# PCB0814.net
KiCad netlist of a schematic drawn in Altium Designer
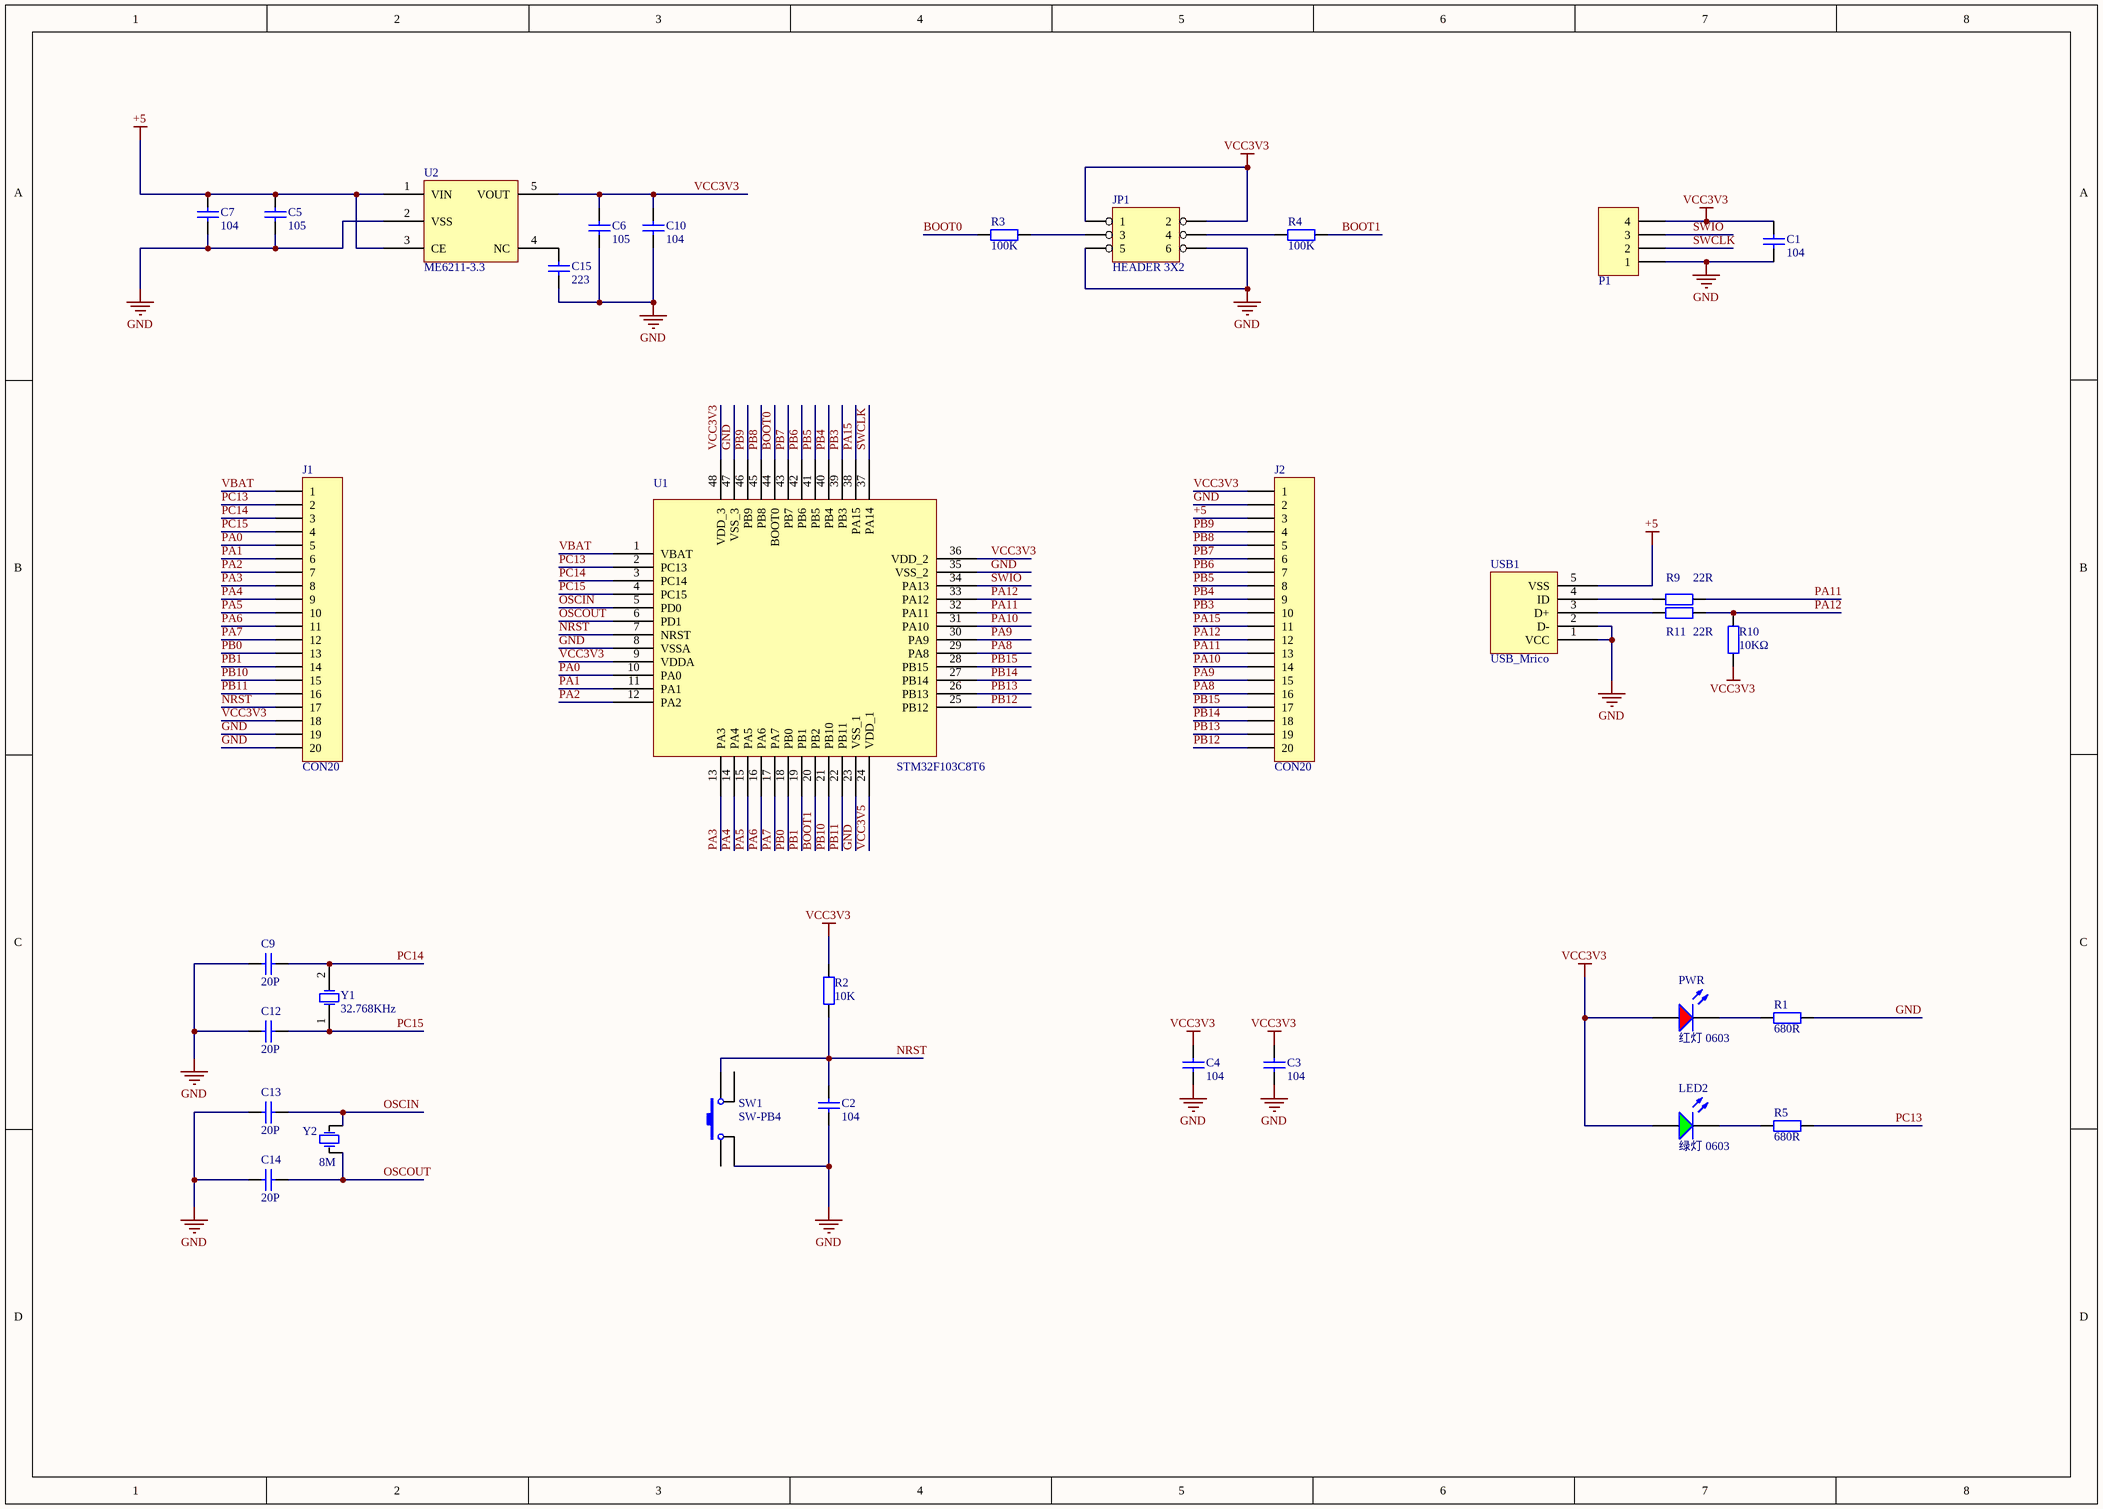
[diagram p0: PCB0814.SchDoc]

(export (version "E")
  (design (tool "Eeschema 10.0.6"))
  (components
    (comp (ref "C1")
      (value "104")
      (footprint "0603_C")
      (description "贴片电容")
      (libsource (lib "Cap") (part "0603 1uF (105) 10% 50V"))
    )
    (comp (ref "C2")
      (value "104")
      (footprint "0603_C")
      (description "贴片电容")
      (libsource (lib "Cap") (part "0603 1uF (105) 10% 50V"))
    )
    (comp (ref "C3")
      (value "104")
      (footprint "0603_C")
      (description "贴片电容")
      (libsource (lib "Cap") (part "0603 68pF (680) 5% 50V"))
    )
    (comp (ref "C4")
      (value "104")
      (footprint "0603_C")
      (description "贴片电容")
      (libsource (lib "Cap") (part "0603 68pF (680) 5% 50V"))
    )
    (comp (ref "C5")
      (value "105")
      (footprint "0603_C")
      (description "贴片电容")
      (libsource (lib "Cap") (part "0603 1uF (105) 10% 50V"))
    )
    (comp (ref "C6")
      (value "105")
      (footprint "0603_C")
      (description "贴片电容")
      (libsource (lib "Cap") (part "0603 1uF (105) 10% 50V"))
    )
    (comp (ref "C7")
      (value "104")
      (footprint "0603_C")
      (description "贴片电容")
      (libsource (lib "Cap") (part "0603 1uF (105) 10% 50V"))
    )
    (comp (ref "C9")
      (value "20P")
      (footprint "0603_C")
      (description "贴片电容")
      (libsource (lib "Cap") (part "0603 68pF (680) 5% 50V"))
    )
    (comp (ref "C10")
      (value "104")
      (footprint "0603_C")
      (description "贴片电容")
      (libsource (lib "Cap") (part "0603 1uF (105) 10% 50V"))
    )
    (comp (ref "C12")
      (value "20P")
      (footprint "0603_C")
      (description "贴片电容")
      (libsource (lib "Cap") (part "0603 68pF (680) 5% 50V"))
    )
    (comp (ref "C13")
      (value "20P")
      (footprint "0603_C")
      (description "贴片电容")
      (libsource (lib "Cap") (part "0603 68pF (680) 5% 50V"))
    )
    (comp (ref "C14")
      (value "20P")
      (footprint "0603_C")
      (description "贴片电容")
      (libsource (lib "Cap") (part "0603 68pF (680) 5% 50V"))
    )
    (comp (ref "C15")
      (value "223")
      (footprint "0603_C")
      (description "贴片电容")
      (libsource (lib "Cap") (part "0603 1uF (105) 10% 50V"))
    )
    (comp (ref "J1")
      (value "CON20")
      (footprint "HDR1X20")
      (description "Connector")
      (libsource (lib "Miscellaneous Devices") (part "CON20"))
    )
    (comp (ref "J2")
      (value "CON20")
      (footprint "HDR1X20")
      (description "Connector")
      (libsource (lib "Miscellaneous Devices") (part "CON20"))
    )
    (comp (ref "JP1")
      (value "HEADER 3X2")
      (footprint "HDR2X3")
      (libsource (lib "Miscellaneous Devices") (part "HEADER 3X2"))
    )
    (comp (ref "LED2")
      (value "绿灯 0603")
      (footprint "0603_LED_S1")
      (description "发光二极管")
      (libsource (lib "LED") (part "0603 绿灯"))
    )
    (comp (ref "P1")
      (value "Header 4")
      (footprint "HDR4X1_A")
      (description "接插件")
      (fields (field (name "PUBLISHER") "Altium Limited"))
      (libsource (lib "Fszhang") (part "Header 4"))
    )
    (comp (ref "PWR")
      (value "红灯 0603")
      (footprint "0603_LED_S1")
      (description "发光二极管")
      (libsource (lib "LED") (part "0603 红灯"))
    )
    (comp (ref "R1")
      (value "680R")
      (footprint "0603_R")
      (description "贴片电阻")
      (libsource (lib "RES") (part "0603 1KΩ (1001) 1%"))
    )
    (comp (ref "R2")
      (value "10K")
      (footprint "0603_R")
      (description "贴片电阻")
      (libsource (lib "") (part "0603 1KΩ (1001) 1%_1"))
    )
    (comp (ref "R3")
      (value "100K")
      (footprint "0603_R")
      (description "贴片电阻")
      (libsource (lib "RES") (part "0603 1KΩ (1001) 1%"))
    )
    (comp (ref "R4")
      (value "100K")
      (footprint "0603_R")
      (description "贴片电阻")
      (libsource (lib "RES") (part "0603 1KΩ (1001) 1%"))
    )
    (comp (ref "R5")
      (value "680R")
      (footprint "0603_R")
      (description "贴片电阻")
      (libsource (lib "RES") (part "0603 1KΩ (1001) 1%"))
    )
    (comp (ref "R9")
      (value "22R")
      (footprint "0603_R")
      (description "贴片电阻")
      (libsource (lib "RES") (part "0603 22Ω (22R0) 1%"))
    )
    (comp (ref "R10")
      (value "10KΩ")
      (footprint "0603_R")
      (description "贴片电阻")
      (libsource (lib "RES") (part "0603 2KΩ (2001) 1%"))
    )
    (comp (ref "R11")
      (value "22R")
      (footprint "0603_R")
      (description "贴片电阻")
      (libsource (lib "RES") (part "0603 22Ω (22R0) 1%"))
    )
    (comp (ref "SW1")
      (value "SW-PB4")
      (footprint "SW_PB4_A1")
      (description "微动开关")
      (fields (field (name "PUBLISHER") "Altium Limited"))
      (libsource (lib "Fszhang") (part "SW-PB4"))
    )
    (comp (ref "U1")
      (value "STM32F103C8T6")
      (footprint "LQFP-48")
      (libsource (lib "PCB0814") (part "STM32F103C8T6"))
    )
    (comp (ref "U2")
      (value "ME6211-3.3")
      (footprint "SOT-23-5")
      (libsource (lib "PCB0814") (part "ME6211-3.3"))
    )
    (comp (ref "USB1")
      (value "USB_Mrico")
      (footprint "USB_MICRO")
      (description "MicroUSB接口")
      (libsource (lib "Fszhang") (part "USB_M"))
    )
    (comp (ref "Y1")
      (value "32.768KHz")
      (footprint "SMD-5032_2P")
      (description "贴片晶振")
      (libsource (lib "Miscellaneous Devices LC") (part "SMD-5032_2P 11.0592MHZ 20PF 20PPM"))
    )
    (comp (ref "Y2")
      (value "8M")
      (footprint "X-SM49")
      (description "晶振")
      (fields (field (name "Comment") "XTAL") (field (name "PUBLISHER") "Altium Limited"))
      (libsource (lib "Fszhang") (part "XTAL"))
    )
  )
  (nets
    (net (code "1") (name "+5") (class "Default")
      (node (ref "C5") (pin "2") (pinfunction "2_2") (pintype "passive"))
      (node (ref "C7") (pin "2") (pinfunction "2_2") (pintype "passive"))
      (node (ref "J2") (pin "3") (pinfunction "3_3") (pintype "passive"))
      (node (ref "U2") (pin "1") (pinfunction "VIN_1") (pintype "passive"))
      (node (ref "U2") (pin "3") (pinfunction "CE_3") (pintype "passive"))
      (node (ref "USB1") (pin "5") (pinfunction "VSS_5") (pintype "passive"))
    )
    (net (code "2") (name "/BOOT0") (class "Default")
      (node (ref "R3") (pin "1") (pinfunction "1_1") (pintype "passive"))
      (node (ref "U1") (pin "44") (pinfunction "BOOT0_44") (pintype "passive"))
    )
    (net (code "3") (name "/BOOT1") (class "Default")
      (node (ref "R4") (pin "2") (pinfunction "2_2") (pintype "passive"))
      (node (ref "U1") (pin "20") (pinfunction "PB2_20") (pintype "passive"))
    )
    (net (code "4") (name "/NRST") (class "Default")
      (node (ref "C2") (pin "2") (pinfunction "2_2") (pintype "passive"))
      (node (ref "J1") (pin "17") (pinfunction "17_17") (pintype "passive"))
      (node (ref "R2") (pin "1") (pinfunction "1_1") (pintype "passive"))
      (node (ref "SW1") (pin "2") (pinfunction "2_2") (pintype "passive"))
      (node (ref "U1") (pin "7") (pinfunction "NRST_7") (pintype "passive"))
    )
    (net (code "5") (name "/OSCIN") (class "Default")
      (node (ref "C13") (pin "2") (pinfunction "2_2") (pintype "passive"))
      (node (ref "U1") (pin "5") (pinfunction "PD0_5") (pintype "passive"))
      (node (ref "Y2") (pin "2") (pinfunction "OSC2_2") (pintype "passive"))
    )
    (net (code "6") (name "/OSCOUT") (class "Default")
      (node (ref "C14") (pin "2") (pinfunction "2_2") (pintype "passive"))
      (node (ref "U1") (pin "6") (pinfunction "PD1_6") (pintype "passive"))
      (node (ref "Y2") (pin "1") (pinfunction "OSC1_1") (pintype "passive"))
    )
    (net (code "7") (name "/PA0") (class "Default")
      (node (ref "J1") (pin "5") (pinfunction "5_5") (pintype "passive"))
      (node (ref "U1") (pin "10") (pinfunction "PA0_10") (pintype "passive"))
    )
    (net (code "8") (name "/PA1") (class "Default")
      (node (ref "J1") (pin "6") (pinfunction "6_6") (pintype "passive"))
      (node (ref "U1") (pin "11") (pinfunction "PA1_11") (pintype "passive"))
    )
    (net (code "9") (name "/PA2") (class "Default")
      (node (ref "J1") (pin "7") (pinfunction "7_7") (pintype "passive"))
      (node (ref "U1") (pin "12") (pinfunction "PA2_12") (pintype "passive"))
    )
    (net (code "10") (name "/PA3") (class "Default")
      (node (ref "J1") (pin "8") (pinfunction "8_8") (pintype "passive"))
      (node (ref "U1") (pin "13") (pinfunction "PA3_13") (pintype "passive"))
    )
    (net (code "11") (name "/PA4") (class "Default")
      (node (ref "J1") (pin "9") (pinfunction "9_9") (pintype "passive"))
      (node (ref "U1") (pin "14") (pinfunction "PA4_14") (pintype "passive"))
    )
    (net (code "12") (name "/PA5") (class "Default")
      (node (ref "J1") (pin "10") (pinfunction "10_10") (pintype "passive"))
      (node (ref "U1") (pin "15") (pinfunction "PA5_15") (pintype "passive"))
    )
    (net (code "13") (name "/PA6") (class "Default")
      (node (ref "J1") (pin "11") (pinfunction "11_11") (pintype "passive"))
      (node (ref "U1") (pin "16") (pinfunction "PA6_16") (pintype "passive"))
    )
    (net (code "14") (name "/PA7") (class "Default")
      (node (ref "J1") (pin "12") (pinfunction "12_12") (pintype "passive"))
      (node (ref "U1") (pin "17") (pinfunction "PA7_17") (pintype "passive"))
    )
    (net (code "15") (name "/PA8") (class "Default")
      (node (ref "J2") (pin "16") (pinfunction "16_16") (pintype "passive"))
      (node (ref "U1") (pin "29") (pinfunction "PA8_29") (pintype "passive"))
    )
    (net (code "16") (name "/PA9") (class "Default")
      (node (ref "J2") (pin "15") (pinfunction "15_15") (pintype "passive"))
      (node (ref "U1") (pin "30") (pinfunction "PA9_30") (pintype "passive"))
    )
    (net (code "17") (name "/PA10") (class "Default")
      (node (ref "J2") (pin "14") (pinfunction "14_14") (pintype "passive"))
      (node (ref "U1") (pin "31") (pinfunction "PA10_31") (pintype "passive"))
    )
    (net (code "18") (name "/PA11") (class "Default")
      (node (ref "J2") (pin "13") (pinfunction "13_13") (pintype "passive"))
      (node (ref "R9") (pin "2") (pinfunction "2_2") (pintype "passive"))
      (node (ref "U1") (pin "32") (pinfunction "PA11_32") (pintype "passive"))
    )
    (net (code "19") (name "/PA12") (class "Default")
      (node (ref "J2") (pin "12") (pinfunction "12_12") (pintype "passive"))
      (node (ref "R10") (pin "2") (pinfunction "2_2") (pintype "passive"))
      (node (ref "R11") (pin "2") (pinfunction "2_2") (pintype "passive"))
      (node (ref "U1") (pin "33") (pinfunction "PA12_33") (pintype "passive"))
    )
    (net (code "20") (name "/PA15") (class "Default")
      (node (ref "J2") (pin "11") (pinfunction "11_11") (pintype "passive"))
      (node (ref "U1") (pin "38") (pinfunction "PA15_38") (pintype "passive"))
    )
    (net (code "21") (name "/PB0") (class "Default")
      (node (ref "J1") (pin "13") (pinfunction "13_13") (pintype "passive"))
      (node (ref "U1") (pin "18") (pinfunction "PB0_18") (pintype "passive"))
    )
    (net (code "22") (name "/PB1") (class "Default")
      (node (ref "J1") (pin "14") (pinfunction "14_14") (pintype "passive"))
      (node (ref "U1") (pin "19") (pinfunction "PB1_19") (pintype "passive"))
    )
    (net (code "23") (name "/PB3") (class "Default")
      (node (ref "J2") (pin "10") (pinfunction "10_10") (pintype "passive"))
      (node (ref "U1") (pin "39") (pinfunction "PB3_39") (pintype "passive"))
    )
    (net (code "24") (name "/PB4") (class "Default")
      (node (ref "J2") (pin "9") (pinfunction "9_9") (pintype "passive"))
      (node (ref "U1") (pin "40") (pinfunction "PB4_40") (pintype "passive"))
    )
    (net (code "25") (name "/PB5") (class "Default")
      (node (ref "J2") (pin "8") (pinfunction "8_8") (pintype "passive"))
      (node (ref "U1") (pin "41") (pinfunction "PB5_41") (pintype "passive"))
    )
    (net (code "26") (name "/PB6") (class "Default")
      (node (ref "J2") (pin "7") (pinfunction "7_7") (pintype "passive"))
      (node (ref "U1") (pin "42") (pinfunction "PB6_42") (pintype "passive"))
    )
    (net (code "27") (name "/PB7") (class "Default")
      (node (ref "J2") (pin "6") (pinfunction "6_6") (pintype "passive"))
      (node (ref "U1") (pin "43") (pinfunction "PB7_43") (pintype "passive"))
    )
    (net (code "28") (name "/PB8") (class "Default")
      (node (ref "J2") (pin "5") (pinfunction "5_5") (pintype "passive"))
      (node (ref "U1") (pin "45") (pinfunction "PB8_45") (pintype "passive"))
    )
    (net (code "29") (name "/PB9") (class "Default")
      (node (ref "J2") (pin "4") (pinfunction "4_4") (pintype "passive"))
      (node (ref "U1") (pin "46") (pinfunction "PB9_46") (pintype "passive"))
    )
    (net (code "30") (name "/PB10") (class "Default")
      (node (ref "J1") (pin "15") (pinfunction "15_15") (pintype "passive"))
      (node (ref "U1") (pin "21") (pinfunction "PB10_21") (pintype "passive"))
    )
    (net (code "31") (name "/PB11") (class "Default")
      (node (ref "J1") (pin "16") (pinfunction "16_16") (pintype "passive"))
      (node (ref "U1") (pin "22") (pinfunction "PB11_22") (pintype "passive"))
    )
    (net (code "32") (name "/PB12") (class "Default")
      (node (ref "J2") (pin "20") (pinfunction "20_20") (pintype "passive"))
      (node (ref "U1") (pin "25") (pinfunction "PB12_25") (pintype "passive"))
    )
    (net (code "33") (name "/PB13") (class "Default")
      (node (ref "J2") (pin "19") (pinfunction "19_19") (pintype "passive"))
      (node (ref "U1") (pin "26") (pinfunction "PB13_26") (pintype "passive"))
    )
    (net (code "34") (name "/PB14") (class "Default")
      (node (ref "J2") (pin "18") (pinfunction "18_18") (pintype "passive"))
      (node (ref "U1") (pin "27") (pinfunction "PB14_27") (pintype "passive"))
    )
    (net (code "35") (name "/PB15") (class "Default")
      (node (ref "J2") (pin "17") (pinfunction "17_17") (pintype "passive"))
      (node (ref "U1") (pin "28") (pinfunction "PB15_28") (pintype "passive"))
    )
    (net (code "36") (name "/PC13") (class "Default")
      (node (ref "J1") (pin "2") (pinfunction "2_2") (pintype "passive"))
      (node (ref "R5") (pin "2") (pinfunction "2_2") (pintype "passive"))
      (node (ref "U1") (pin "2") (pinfunction "PC13_2") (pintype "passive"))
    )
    (net (code "37") (name "/PC14") (class "Default")
      (node (ref "C9") (pin "2") (pinfunction "2_2") (pintype "passive"))
      (node (ref "J1") (pin "3") (pinfunction "3_3") (pintype "passive"))
      (node (ref "U1") (pin "3") (pinfunction "PC14_3") (pintype "passive"))
      (node (ref "Y1") (pin "2") (pinfunction "OSC2_2") (pintype "passive"))
    )
    (net (code "38") (name "/PC15") (class "Default")
      (node (ref "C12") (pin "2") (pinfunction "2_2") (pintype "passive"))
      (node (ref "J1") (pin "4") (pinfunction "4_4") (pintype "passive"))
      (node (ref "U1") (pin "4") (pinfunction "PC15_4") (pintype "passive"))
      (node (ref "Y1") (pin "1") (pinfunction "OSC1_1") (pintype "passive"))
    )
    (net (code "39") (name "/SWCLK") (class "Default")
      (node (ref "P1") (pin "2") (pinfunction "2_2") (pintype "passive"))
      (node (ref "U1") (pin "37") (pinfunction "PA14_37") (pintype "passive"))
    )
    (net (code "40") (name "/SWIO") (class "Default")
      (node (ref "P1") (pin "3") (pinfunction "3_3") (pintype "passive"))
      (node (ref "U1") (pin "34") (pinfunction "PA13_34") (pintype "passive"))
    )
    (net (code "41") (name "/VBAT") (class "Default")
      (node (ref "J1") (pin "1") (pinfunction "1_1") (pintype "passive"))
      (node (ref "U1") (pin "1") (pinfunction "VBAT_1") (pintype "passive"))
    )
    (net (code "42") (name "/VCC3V5") (class "Default")
      (node (ref "U1") (pin "24") (pinfunction "VDD_1_24") (pintype "passive"))
    )
    (net (code "43") (name "GND") (class "Default")
      (node (ref "C1") (pin "2") (pinfunction "2_2") (pintype "passive"))
      (node (ref "C10") (pin "1") (pinfunction "1_1") (pintype "passive"))
      (node (ref "C12") (pin "1") (pinfunction "1_1") (pintype "passive"))
      (node (ref "C13") (pin "1") (pinfunction "1_1") (pintype "passive"))
      (node (ref "C14") (pin "1") (pinfunction "1_1") (pintype "passive"))
      (node (ref "C15") (pin "1") (pinfunction "1_1") (pintype "passive"))
      (node (ref "C2") (pin "1") (pinfunction "1_1") (pintype "passive"))
      (node (ref "C3") (pin "2") (pinfunction "2_2") (pintype "passive"))
      (node (ref "C4") (pin "2") (pinfunction "2_2") (pintype "passive"))
      (node (ref "C5") (pin "1") (pinfunction "1_1") (pintype "passive"))
      (node (ref "C6") (pin "1") (pinfunction "1_1") (pintype "passive"))
      (node (ref "C7") (pin "1") (pinfunction "1_1") (pintype "passive"))
      (node (ref "C9") (pin "1") (pinfunction "1_1") (pintype "passive"))
      (node (ref "J1") (pin "19") (pinfunction "19_19") (pintype "passive"))
      (node (ref "J1") (pin "20") (pinfunction "20_20") (pintype "passive"))
      (node (ref "J2") (pin "2") (pinfunction "2_2") (pintype "passive"))
      (node (ref "JP1") (pin "5") (pinfunction "5_5") (pintype "passive"))
      (node (ref "JP1") (pin "6") (pinfunction "6_6") (pintype "passive"))
      (node (ref "P1") (pin "1") (pinfunction "1_1") (pintype "passive"))
      (node (ref "R1") (pin "2") (pinfunction "2_2") (pintype "passive"))
      (node (ref "SW1") (pin "4") (pinfunction "4_4") (pintype "passive"))
      (node (ref "U1") (pin "23") (pinfunction "VSS_1_23") (pintype "passive"))
      (node (ref "U1") (pin "35") (pinfunction "VSS_2_35") (pintype "passive"))
      (node (ref "U1") (pin "47") (pinfunction "VSS_3_47") (pintype "passive"))
      (node (ref "U1") (pin "8") (pinfunction "VSSA_8") (pintype "passive"))
      (node (ref "U2") (pin "2") (pinfunction "VSS_2") (pintype "passive"))
      (node (ref "USB1") (pin "1") (pinfunction "VCC_1") (pintype "passive"))
      (node (ref "USB1") (pin "2") (pinfunction "D-_2") (pintype "passive"))
    )
    (net (code "44") (name "Net-(JP1-Pad3)") (class "Default")
      (node (ref "JP1") (pin "3") (pinfunction "3_3") (pintype "passive"))
      (node (ref "R3") (pin "2") (pinfunction "2_2") (pintype "passive"))
    )
    (net (code "45") (name "Net-(JP1-Pad4)") (class "Default")
      (node (ref "JP1") (pin "4") (pinfunction "4_4") (pintype "passive"))
      (node (ref "R4") (pin "1") (pinfunction "1_1") (pintype "passive"))
    )
    (net (code "46") (name "Net-(LED2-PadK)") (class "Default")
      (node (ref "LED2") (pin "K") (pinfunction "K_K") (pintype "passive"))
      (node (ref "R5") (pin "1") (pinfunction "1_1") (pintype "passive"))
    )
    (net (code "47") (name "Net-(PWR-PadK)") (class "Default")
      (node (ref "PWR") (pin "K") (pinfunction "K_K") (pintype "passive"))
      (node (ref "R1") (pin "1") (pinfunction "1_1") (pintype "passive"))
    )
    (net (code "48") (name "Net-(U2-NC)") (class "Default")
      (node (ref "C15") (pin "2") (pinfunction "2_2") (pintype "passive"))
      (node (ref "U2") (pin "4") (pinfunction "NC_4") (pintype "passive"))
    )
    (net (code "49") (name "Net-(USB1-D+)") (class "Default")
      (node (ref "R11") (pin "1") (pinfunction "1_1") (pintype "passive"))
      (node (ref "USB1") (pin "3") (pinfunction "D+_3") (pintype "passive"))
    )
    (net (code "50") (name "Net-(USB1-ID)") (class "Default")
      (node (ref "R9") (pin "1") (pinfunction "1_1") (pintype "passive"))
      (node (ref "USB1") (pin "4") (pinfunction "ID_4") (pintype "passive"))
    )
    (net (code "51") (name "VCC3V3") (class "Default")
      (node (ref "C1") (pin "1") (pinfunction "1_1") (pintype "passive"))
      (node (ref "C10") (pin "2") (pinfunction "2_2") (pintype "passive"))
      (node (ref "C3") (pin "1") (pinfunction "1_1") (pintype "passive"))
      (node (ref "C4") (pin "1") (pinfunction "1_1") (pintype "passive"))
      (node (ref "C6") (pin "2") (pinfunction "2_2") (pintype "passive"))
      (node (ref "J1") (pin "18") (pinfunction "18_18") (pintype "passive"))
      (node (ref "J2") (pin "1") (pinfunction "1_1") (pintype "passive"))
      (node (ref "JP1") (pin "1") (pinfunction "1_1") (pintype "passive"))
      (node (ref "JP1") (pin "2") (pinfunction "2_2") (pintype "passive"))
      (node (ref "LED2") (pin "A") (pinfunction "A_A") (pintype "passive"))
      (node (ref "P1") (pin "4") (pinfunction "4_4") (pintype "passive"))
      (node (ref "PWR") (pin "A") (pinfunction "A_A") (pintype "passive"))
      (node (ref "R10") (pin "1") (pinfunction "1_1") (pintype "passive"))
      (node (ref "R2") (pin "2") (pinfunction "2_2") (pintype "passive"))
      (node (ref "U1") (pin "36") (pinfunction "VDD_2_36") (pintype "passive"))
      (node (ref "U1") (pin "48") (pinfunction "VDD_3_48") (pintype "passive"))
      (node (ref "U1") (pin "9") (pinfunction "VDDA_9") (pintype "passive"))
      (node (ref "U2") (pin "5") (pinfunction "VOUT_5") (pintype "passive"))
    )
    (net (code "52") (name "unconnected-(SW1-Pad1)") (class "Default")
      (node (ref "SW1") (pin "1") (pinfunction "1_1") (pintype "passive"))
    )
    (net (code "53") (name "unconnected-(SW1-Pad3)") (class "Default")
      (node (ref "SW1") (pin "3") (pinfunction "3_3") (pintype "passive"))
    )
  )
)
